# guageboard.net
KiCad netlist of a schematic drawn in EAGLE
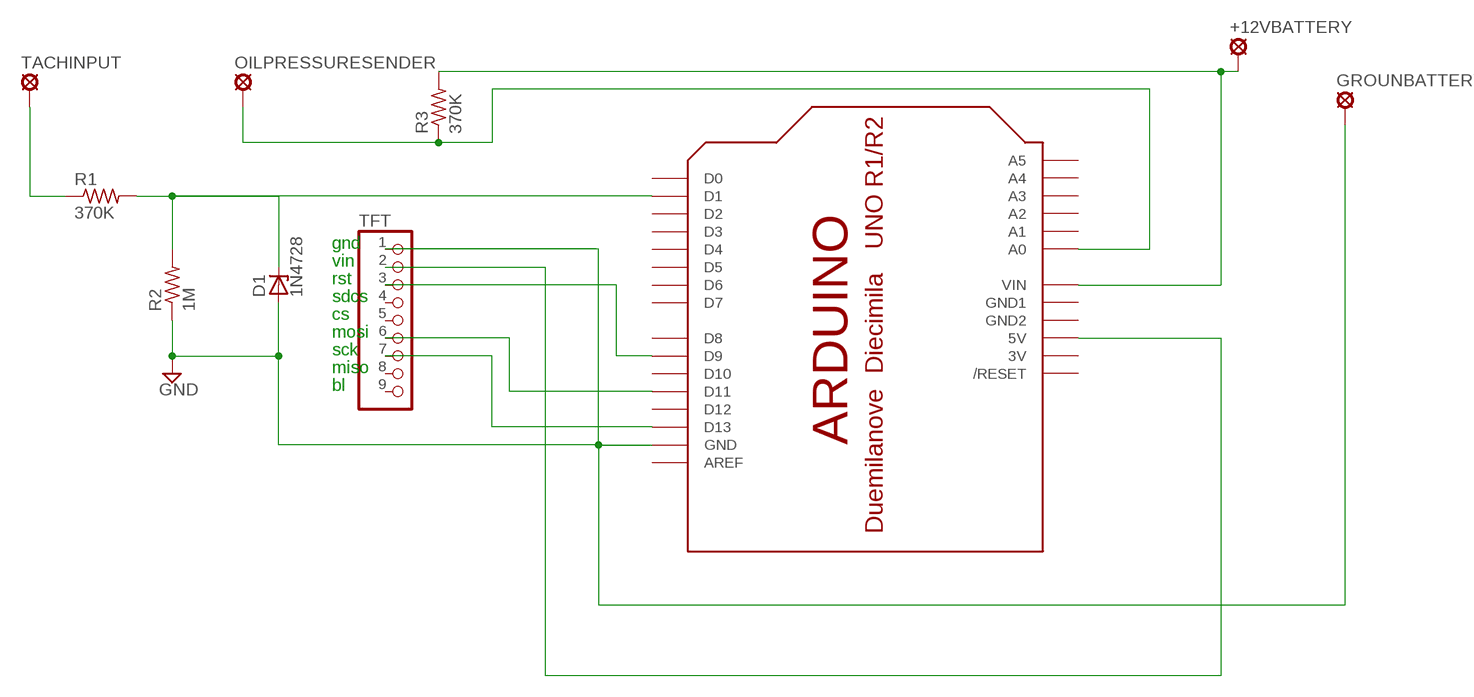
[diagram p0: schematic, sheet 1]

(export (version "E")
  (design (tool "Eeschema 10.0.6"))
  (components
    (comp (ref "+12VBATTERY")
      (value "MCS10B")
      (footprint "eagle-import:MCS10B")
      (libsource (lib "eagle-import") (part "MCS10B"))
    )
    (comp (ref "D1")
      (value "1N4728")
      (footprint "eagle-import:DO41Z10")
      (libsource (lib "eagle-import") (part "1N4728"))
    )
    (comp (ref "GROUNBATTERY")
      (value "MCS10B")
      (footprint "eagle-import:MCS10B")
      (libsource (lib "eagle-import") (part "MCS10B"))
    )
    (comp (ref "OILPRESSURESENDER")
      (value "MCS10B")
      (footprint "eagle-import:MCS10B")
      (libsource (lib "eagle-import") (part "MCS10B"))
    )
    (comp (ref "R1")
      (value "370K")
      (footprint "eagle-import:0204_5")
      (libsource (lib "eagle-import") (part "R-US_0204/5"))
    )
    (comp (ref "R2")
      (value "1M")
      (footprint "eagle-import:0204_5")
      (libsource (lib "eagle-import") (part "R-US_0204/5"))
    )
    (comp (ref "R3")
      (value "370K")
      (footprint "eagle-import:0204_5")
      (libsource (lib "eagle-import") (part "R-US_0204/5"))
    )
    (comp (ref "TACHINPUT")
      (value "MCS10B")
      (footprint "eagle-import:MCS10B")
      (libsource (lib "eagle-import") (part "MCS10B"))
    )
    (comp (ref "TFT")
      (value "PINHD-1X9")
      (footprint "eagle-import:1X09-BIG")
      (libsource (lib "eagle-import") (part "PINHD-1X9"))
    )
    (comp (ref "U$1")
      (value "ARDUINOUNO")
      (footprint "eagle-import:ARDUINO")
      (libsource (lib "eagle-import") (part "ARDUINOUNO"))
    )
  )
  (nets
    (net (code "1") (name "/3V") (class "Default")
      (node (ref "U$1") (pin "3V") (pinfunction "3V_3V") (pintype "power_in"))
    )
    (net (code "2") (name "/GND1") (class "Default")
      (node (ref "U$1") (pin "GND1") (pinfunction "GND1_GND1") (pintype "power_in"))
    )
    (net (code "3") (name "/GND2") (class "Default")
      (node (ref "U$1") (pin "GND2") (pinfunction "GND2_GND2") (pintype "power_in"))
    )
    (net (code "4") (name "GND") (class "Default")
      (node (ref "D1") (pin "A") (pinfunction "A_A") (pintype "passive"))
      (node (ref "GROUNBATTERY") (pin "MP") (pinfunction "MP_MP") (pintype "passive"))
      (node (ref "R2") (pin "1") (pinfunction "1_1") (pintype "passive"))
      (node (ref "TFT") (pin "1") (pinfunction "1_1") (pintype "passive"))
      (node (ref "U$1") (pin "GND") (pinfunction "GND_GND") (pintype "power_in"))
    )
    (net (code "5") (name "Net-(+12VBATTERY-PadMP)") (class "Default")
      (node (ref "+12VBATTERY") (pin "MP") (pinfunction "MP_MP") (pintype "passive"))
      (node (ref "R3") (pin "2") (pinfunction "2_2") (pintype "passive"))
      (node (ref "U$1") (pin "VIN") (pinfunction "VIN_VIN") (pintype "power_in"))
    )
    (net (code "6") (name "Net-(D1-PadC)") (class "Default")
      (node (ref "D1") (pin "C") (pinfunction "C_C") (pintype "passive"))
      (node (ref "R1") (pin "2") (pinfunction "2_2") (pintype "passive"))
      (node (ref "R2") (pin "2") (pinfunction "2_2") (pintype "passive"))
      (node (ref "U$1") (pin "D1") (pinfunction "D1_D1") (pintype "bidirectional"))
    )
    (net (code "7") (name "Net-(OILPRESSURESENDER-PadMP)") (class "Default")
      (node (ref "OILPRESSURESENDER") (pin "MP") (pinfunction "MP_MP") (pintype "passive"))
      (node (ref "R3") (pin "1") (pinfunction "1_1") (pintype "passive"))
      (node (ref "U$1") (pin "A0") (pinfunction "A0_A0") (pintype "bidirectional"))
    )
    (net (code "8") (name "Net-(R1-Pad1)") (class "Default")
      (node (ref "R1") (pin "1") (pinfunction "1_1") (pintype "passive"))
      (node (ref "TACHINPUT") (pin "MP") (pinfunction "MP_MP") (pintype "passive"))
    )
    (net (code "9") (name "Net-(TFT-Pad2)") (class "Default")
      (node (ref "TFT") (pin "2") (pinfunction "2_2") (pintype "passive"))
      (node (ref "U$1") (pin "5V") (pinfunction "5V_5V") (pintype "power_in"))
    )
    (net (code "10") (name "Net-(TFT-Pad3)") (class "Default")
      (node (ref "TFT") (pin "3") (pinfunction "3_3") (pintype "passive"))
      (node (ref "U$1") (pin "D9") (pinfunction "D9_D9") (pintype "bidirectional"))
    )
    (net (code "11") (name "Net-(TFT-Pad6)") (class "Default")
      (node (ref "TFT") (pin "6") (pinfunction "6_6") (pintype "passive"))
      (node (ref "U$1") (pin "D11") (pinfunction "D11_D11") (pintype "bidirectional"))
    )
    (net (code "12") (name "Net-(TFT-Pad7)") (class "Default")
      (node (ref "TFT") (pin "7") (pinfunction "7_7") (pintype "passive"))
      (node (ref "U$1") (pin "D13") (pinfunction "D13_D13") (pintype "bidirectional"))
    )
    (net (code "13") (name "unconnected-(TFT-Pad4)") (class "Default")
      (node (ref "TFT") (pin "4") (pinfunction "4_4") (pintype "passive"))
    )
    (net (code "14") (name "unconnected-(TFT-Pad5)") (class "Default")
      (node (ref "TFT") (pin "5") (pinfunction "5_5") (pintype "passive"))
    )
    (net (code "15") (name "unconnected-(TFT-Pad8)") (class "Default")
      (node (ref "TFT") (pin "8") (pinfunction "8_8") (pintype "passive"))
    )
    (net (code "16") (name "unconnected-(TFT-Pad9)") (class "Default")
      (node (ref "TFT") (pin "9") (pinfunction "9_9") (pintype "passive"))
    )
    (net (code "17") (name "unconnected-(U$1-PadA1)") (class "Default")
      (node (ref "U$1") (pin "A1") (pinfunction "A1_A1") (pintype "bidirectional"))
    )
    (net (code "18") (name "unconnected-(U$1-PadA2)") (class "Default")
      (node (ref "U$1") (pin "A2") (pinfunction "A2_A2") (pintype "bidirectional"))
    )
    (net (code "19") (name "unconnected-(U$1-PadA3)") (class "Default")
      (node (ref "U$1") (pin "A3") (pinfunction "A3_A3") (pintype "bidirectional"))
    )
    (net (code "20") (name "unconnected-(U$1-PadA4)") (class "Default")
      (node (ref "U$1") (pin "A4") (pinfunction "A4_A4") (pintype "bidirectional"))
    )
    (net (code "21") (name "unconnected-(U$1-PadA5)") (class "Default")
      (node (ref "U$1") (pin "A5") (pinfunction "A5_A5") (pintype "bidirectional"))
    )
    (net (code "22") (name "unconnected-(U$1-PadAREF)") (class "Default")
      (node (ref "U$1") (pin "AREF") (pinfunction "AREF_AREF") (pintype "bidirectional"))
    )
    (net (code "23") (name "unconnected-(U$1-PadD0)") (class "Default")
      (node (ref "U$1") (pin "D0") (pinfunction "D0_D0") (pintype "bidirectional"))
    )
    (net (code "24") (name "unconnected-(U$1-PadD2)") (class "Default")
      (node (ref "U$1") (pin "D2") (pinfunction "D2_D2") (pintype "bidirectional"))
    )
    (net (code "25") (name "unconnected-(U$1-PadD3)") (class "Default")
      (node (ref "U$1") (pin "D3") (pinfunction "D3_D3") (pintype "bidirectional"))
    )
    (net (code "26") (name "unconnected-(U$1-PadD4)") (class "Default")
      (node (ref "U$1") (pin "D4") (pinfunction "D4_D4") (pintype "bidirectional"))
    )
    (net (code "27") (name "unconnected-(U$1-PadD5)") (class "Default")
      (node (ref "U$1") (pin "D5") (pinfunction "D5_D5") (pintype "bidirectional"))
    )
    (net (code "28") (name "unconnected-(U$1-PadD6)") (class "Default")
      (node (ref "U$1") (pin "D6") (pinfunction "D6_D6") (pintype "bidirectional"))
    )
    (net (code "29") (name "unconnected-(U$1-PadD7)") (class "Default")
      (node (ref "U$1") (pin "D7") (pinfunction "D7_D7") (pintype "bidirectional"))
    )
    (net (code "30") (name "unconnected-(U$1-PadD8)") (class "Default")
      (node (ref "U$1") (pin "D8") (pinfunction "D8_D8") (pintype "bidirectional"))
    )
    (net (code "31") (name "unconnected-(U$1-PadD10)") (class "Default")
      (node (ref "U$1") (pin "D10") (pinfunction "D10_D10") (pintype "bidirectional"))
    )
    (net (code "32") (name "unconnected-(U$1-PadD12)") (class "Default")
      (node (ref "U$1") (pin "D12") (pinfunction "D12_D12") (pintype "bidirectional"))
    )
    (net (code "33") (name "unconnected-(U$1-{slash}RESET-PadRESET)") (class "Default")
      (node (ref "U$1") (pin "RESET") (pinfunction "/RESET_RESET") (pintype "bidirectional"))
    )
  )
)
